# BRD161205.net
KiCad netlist of a schematic drawn in EAGLE
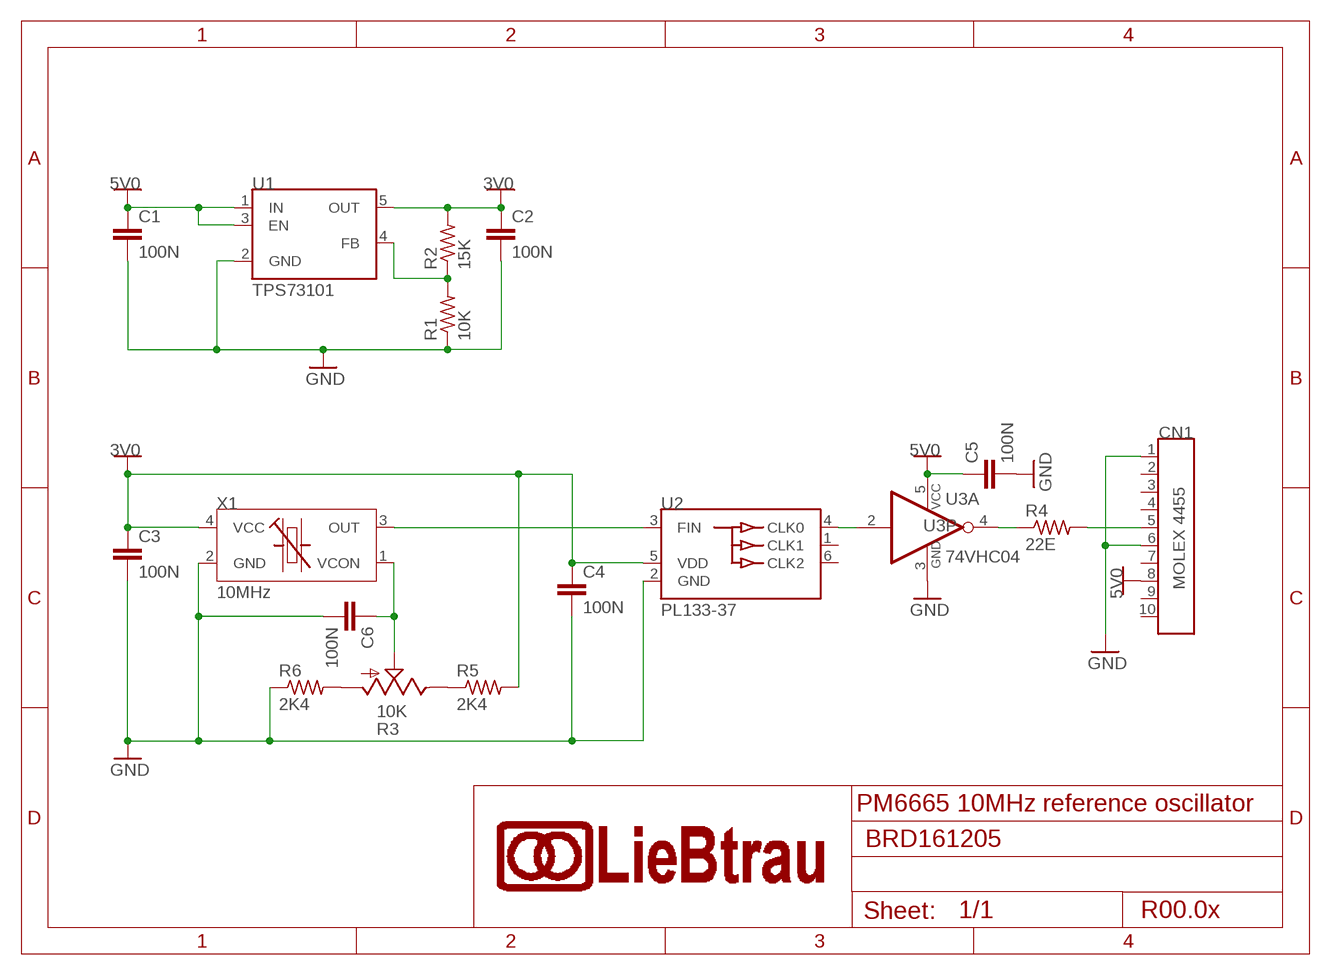
[diagram p0: schematic, sheet 1]

(export (version "E")
  (design (tool "Eeschema 10.0.6"))
  (components
    (comp (ref "C1")
      (value "100N")
      (footprint "eagle-import:CA_1206")
      (libsource (lib "eagle-import") (part "CA1206_100N_"))
    )
    (comp (ref "C2")
      (value "100N")
      (footprint "eagle-import:CA_1206")
      (libsource (lib "eagle-import") (part "CA1206_100N_"))
    )
    (comp (ref "C3")
      (value "100N")
      (footprint "eagle-import:CA_1206")
      (libsource (lib "eagle-import") (part "CA1206_100N_"))
    )
    (comp (ref "C4")
      (value "100N")
      (footprint "eagle-import:CA_1206")
      (libsource (lib "eagle-import") (part "CA1206_100N_"))
    )
    (comp (ref "C5")
      (value "100N")
      (footprint "eagle-import:CA_1206")
      (libsource (lib "eagle-import") (part "CA1206_100N_"))
    )
    (comp (ref "C6")
      (value "100N")
      (footprint "eagle-import:CA_1206")
      (libsource (lib "eagle-import") (part "CA1206_100N_"))
    )
    (comp (ref "CN1")
      (value "MOLEX 4455")
      (footprint "eagle-import:CN_HDR1X10_90D_P254_MOLEX_4455")
      (libsource (lib "eagle-import") (part "CN_10P_MOLEX_4455_"))
    )
    (comp (ref "R1")
      (value "10K")
      (footprint "eagle-import:RE_1206")
      (libsource (lib "eagle-import") (part "RE1206_10K_"))
    )
    (comp (ref "R2")
      (value "15K")
      (footprint "eagle-import:RE_1206")
      (libsource (lib "eagle-import") (part "RE1206_15K_"))
    )
    (comp (ref "R3")
      (value "10K")
      (footprint "eagle-import:RE_TRIM_TH_90D_P25")
      (libsource (lib "eagle-import") (part "RE_TRIMTH_90D_P25_10K_"))
    )
    (comp (ref "R4")
      (value "22E")
      (footprint "eagle-import:RE_1206")
      (libsource (lib "eagle-import") (part "RE1206_22E_"))
    )
    (comp (ref "R5")
      (value "2K4")
      (footprint "eagle-import:RE_1206")
      (libsource (lib "eagle-import") (part "RE1206_2K4_"))
    )
    (comp (ref "R6")
      (value "2K4")
      (footprint "eagle-import:RE_1206")
      (libsource (lib "eagle-import") (part "RE1206_2K4_"))
    )
    (comp (ref "U1")
      (value "TPS73101")
      (footprint "eagle-import:SC_SOT23-5")
      (libsource (lib "eagle-import") (part "IC_TPS73101SOT23-5_TPS73101_"))
    )
    (comp (ref "U2")
      (value "PL133-37")
      (footprint "eagle-import:SC_SOT23-6")
      (libsource (lib "eagle-import") (part "IC_PL133-37SOT23-6_TC-R_"))
    )
    (comp (ref "U3")
      (value "74VHC04")
      (footprint "eagle-import:SC_SOT23-5")
      (libsource (lib "eagle-import") (part "IC_7404SOT23-5_VHC1GT_"))
    )
    (comp (ref "X1")
      (value "10MHz")
      (footprint "eagle-import:XT_3225")
      (libsource (lib "eagle-import") (part "XT_VCTCXO3225_10MHZ_"))
    )
  )
  (nets
    (net (code "1") (name "3V0") (class "Default")
      (node (ref "C2") (pin "1") (pinfunction "1_1") (pintype "passive"))
      (node (ref "C3") (pin "1") (pinfunction "1_1") (pintype "passive"))
      (node (ref "C4") (pin "1") (pinfunction "1_1") (pintype "passive"))
      (node (ref "R2") (pin "2") (pinfunction "2_2") (pintype "passive"))
      (node (ref "R5") (pin "2") (pinfunction "2_2") (pintype "passive"))
      (node (ref "U1") (pin "5") (pinfunction "OUT_5") (pintype "bidirectional"))
      (node (ref "U2") (pin "5") (pinfunction "VDD_5") (pintype "bidirectional"))
      (node (ref "X1") (pin "4") (pinfunction "VCC_4") (pintype "power_in"))
    )
    (net (code "2") (name "5V0") (class "Default")
      (node (ref "C1") (pin "1") (pinfunction "1_1") (pintype "passive"))
      (node (ref "C5") (pin "1") (pinfunction "1_1") (pintype "passive"))
      (node (ref "CN1") (pin "8") (pinfunction "8_8") (pintype "bidirectional"))
      (node (ref "U1") (pin "1") (pinfunction "IN_1") (pintype "bidirectional"))
      (node (ref "U1") (pin "3") (pinfunction "EN_3") (pintype "bidirectional"))
      (node (ref "U3") (pin "5") (pinfunction "VCC_5") (pintype "power_in"))
    )
    (net (code "3") (name "GND") (class "Default")
      (node (ref "C1") (pin "2") (pinfunction "2_2") (pintype "passive"))
      (node (ref "C2") (pin "2") (pinfunction "2_2") (pintype "passive"))
      (node (ref "C3") (pin "2") (pinfunction "2_2") (pintype "passive"))
      (node (ref "C4") (pin "2") (pinfunction "2_2") (pintype "passive"))
      (node (ref "C5") (pin "2") (pinfunction "2_2") (pintype "passive"))
      (node (ref "C6") (pin "2") (pinfunction "2_2") (pintype "passive"))
      (node (ref "CN1") (pin "1") (pinfunction "1_1") (pintype "bidirectional"))
      (node (ref "CN1") (pin "6") (pinfunction "6_6") (pintype "bidirectional"))
      (node (ref "R1") (pin "1") (pinfunction "1_1") (pintype "passive"))
      (node (ref "R6") (pin "1") (pinfunction "1_1") (pintype "passive"))
      (node (ref "U1") (pin "2") (pinfunction "GND_2") (pintype "bidirectional"))
      (node (ref "U2") (pin "2") (pinfunction "GND_2") (pintype "bidirectional"))
      (node (ref "U3") (pin "3") (pinfunction "GND_3") (pintype "power_in"))
      (node (ref "X1") (pin "2") (pinfunction "GND_2") (pintype "power_in"))
    )
    (net (code "4") (name "Net-(CN1-Pad5)") (class "Default")
      (node (ref "CN1") (pin "5") (pinfunction "5_5") (pintype "bidirectional"))
      (node (ref "R4") (pin "2") (pinfunction "2_2") (pintype "passive"))
    )
    (net (code "5") (name "Net-(R3-Pad1)") (class "Default")
      (node (ref "R3") (pin "1") (pinfunction "1_1") (pintype "passive"))
      (node (ref "R6") (pin "2") (pinfunction "2_2") (pintype "passive"))
    )
    (net (code "6") (name "Net-(R3-Pad3)") (class "Default")
      (node (ref "R3") (pin "3") (pinfunction "3_3") (pintype "passive"))
      (node (ref "R5") (pin "1") (pinfunction "1_1") (pintype "passive"))
    )
    (net (code "7") (name "Net-(U1-FB)") (class "Default")
      (node (ref "R1") (pin "2") (pinfunction "2_2") (pintype "passive"))
      (node (ref "R2") (pin "1") (pinfunction "1_1") (pintype "passive"))
      (node (ref "U1") (pin "4") (pinfunction "FB_4") (pintype "bidirectional"))
    )
    (net (code "8") (name "Net-(U2-CLK0)") (class "Default")
      (node (ref "U2") (pin "4") (pinfunction "CLK0_4") (pintype "bidirectional"))
      (node (ref "U3") (pin "2") (pinfunction "I_2") (pintype "input"))
    )
    (net (code "9") (name "Net-(U2-FIN)") (class "Default")
      (node (ref "U2") (pin "3") (pinfunction "FIN_3") (pintype "bidirectional"))
      (node (ref "X1") (pin "3") (pinfunction "OUT_3") (pintype "output"))
    )
    (net (code "10") (name "Net-(U3A-O)") (class "Default")
      (node (ref "R4") (pin "1") (pinfunction "1_1") (pintype "passive"))
      (node (ref "U3") (pin "4") (pinfunction "O_4") (pintype "output"))
    )
    (net (code "11") (name "Net-(X1-VCON)") (class "Default")
      (node (ref "C6") (pin "1") (pinfunction "1_1") (pintype "passive"))
      (node (ref "R3") (pin "2") (pinfunction "2_2") (pintype "passive"))
      (node (ref "X1") (pin "1") (pinfunction "VCON_1") (pintype "output"))
    )
    (net (code "12") (name "unconnected-(CN1-Pad2)") (class "Default")
      (node (ref "CN1") (pin "2") (pinfunction "2_2") (pintype "bidirectional"))
    )
    (net (code "13") (name "unconnected-(CN1-Pad3)") (class "Default")
      (node (ref "CN1") (pin "3") (pinfunction "3_3") (pintype "bidirectional"))
    )
    (net (code "14") (name "unconnected-(CN1-Pad4)") (class "Default")
      (node (ref "CN1") (pin "4") (pinfunction "4_4") (pintype "bidirectional"))
    )
    (net (code "15") (name "unconnected-(CN1-Pad7)") (class "Default")
      (node (ref "CN1") (pin "7") (pinfunction "7_7") (pintype "bidirectional"))
    )
    (net (code "16") (name "unconnected-(CN1-Pad9)") (class "Default")
      (node (ref "CN1") (pin "9") (pinfunction "9_9") (pintype "bidirectional"))
    )
    (net (code "17") (name "unconnected-(CN1-Pad10)") (class "Default")
      (node (ref "CN1") (pin "10") (pinfunction "10_10") (pintype "bidirectional"))
    )
    (net (code "18") (name "unconnected-(U2-CLK1-Pad1)") (class "Default")
      (node (ref "U2") (pin "1") (pinfunction "CLK1_1") (pintype "bidirectional"))
    )
    (net (code "19") (name "unconnected-(U2-CLK2-Pad6)") (class "Default")
      (node (ref "U2") (pin "6") (pinfunction "CLK2_6") (pintype "bidirectional"))
    )
  )
)
